# pc_healthypi_5_2_display_st7796.net
KiCad netlist of a schematic drawn in EAGLE
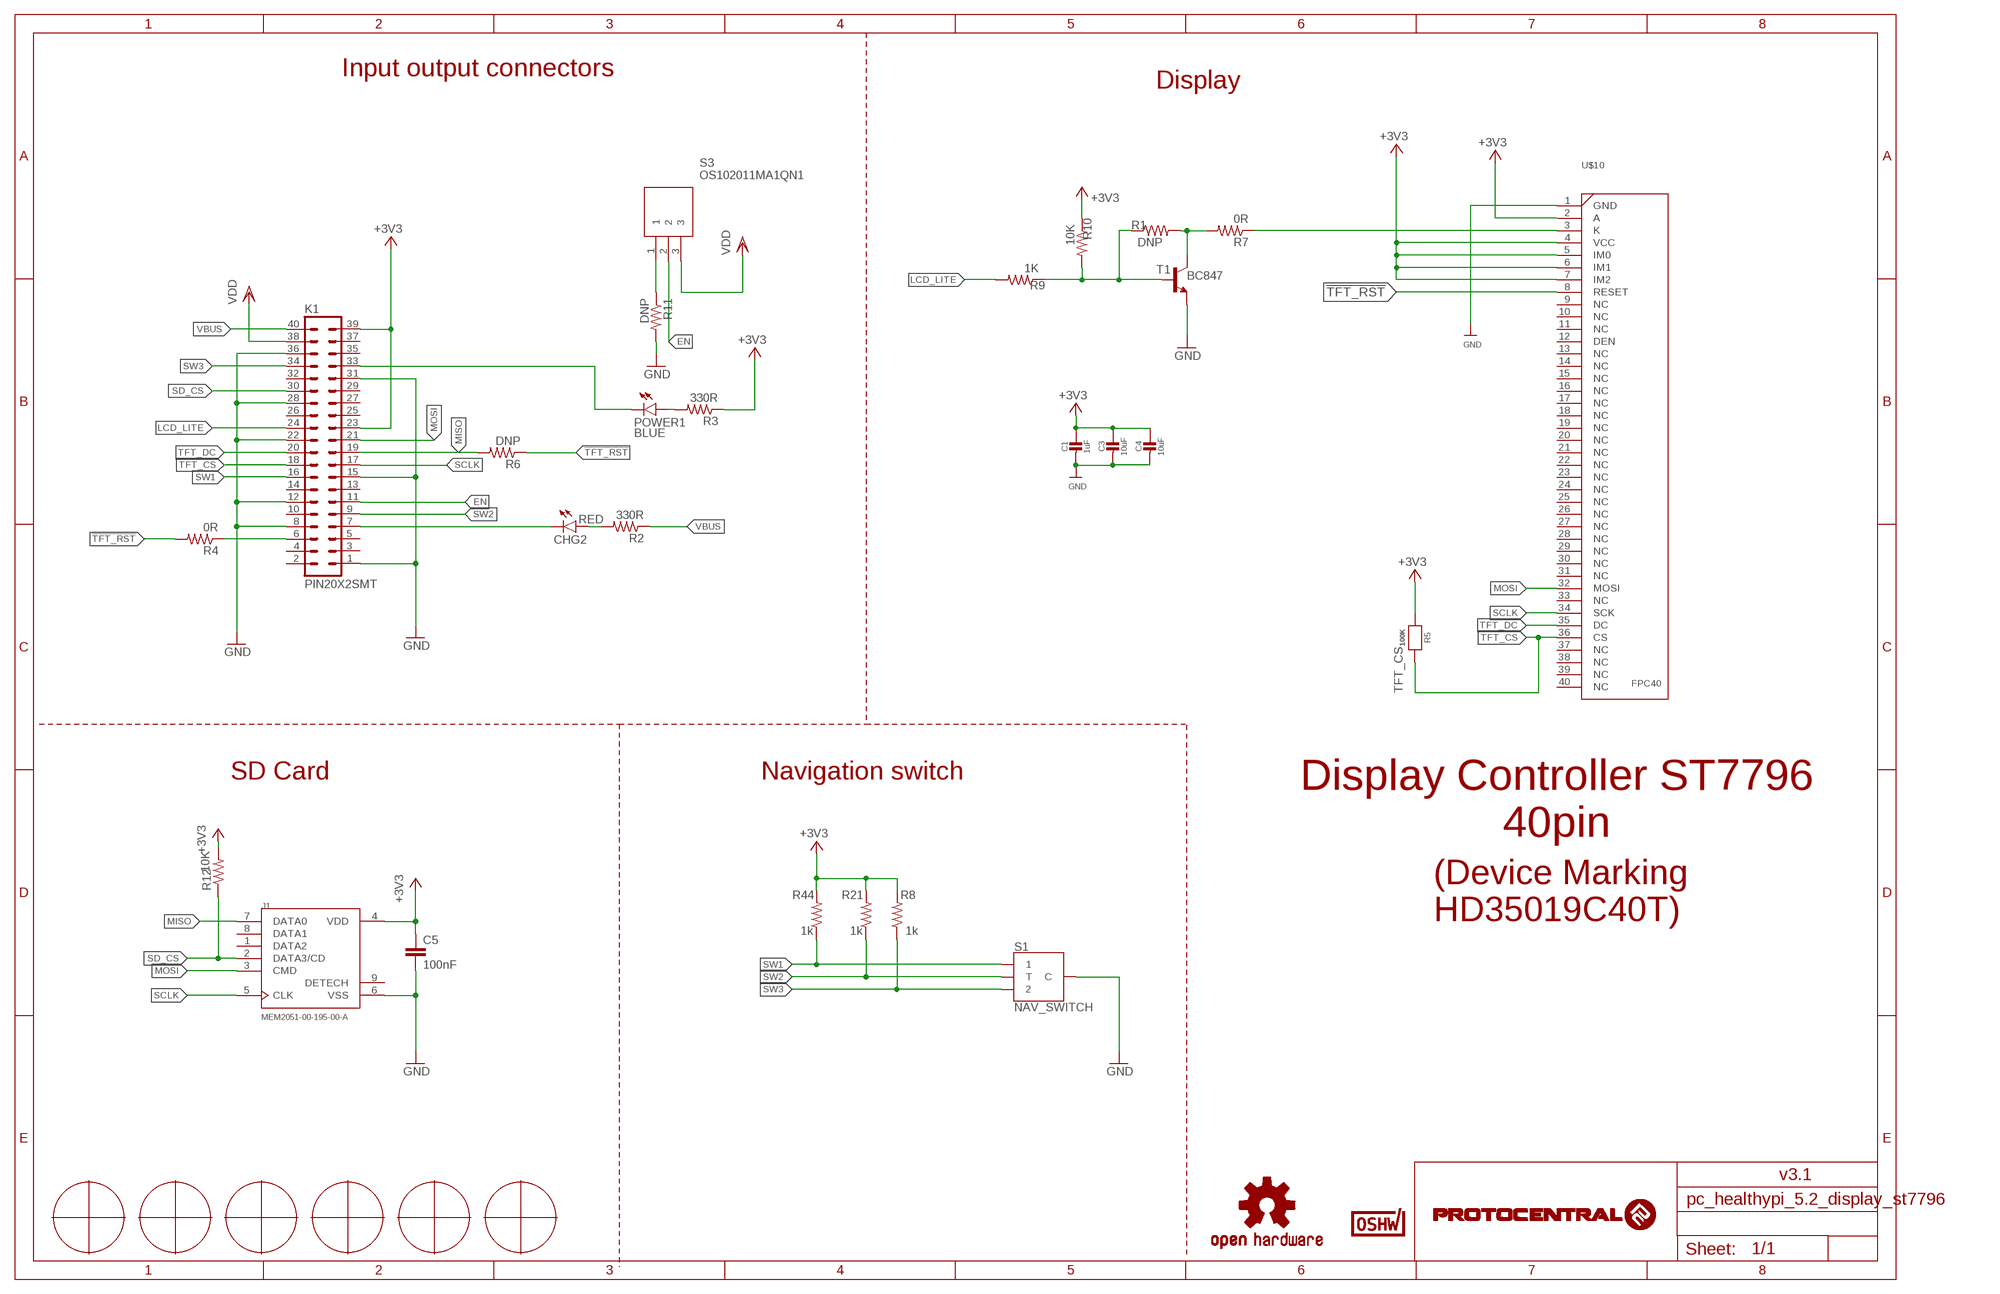
[diagram p0: schematic, sheet 1]

(export (version "E")
  (design (tool "Eeschema 10.0.6"))
  (components
    (comp (ref "C1")
      (value "1uF")
      (footprint "eagle-import:0805-NO")
      (libsource (lib "eagle-import") (part "CAP_CERAMIC0805-NOOUTLINE"))
    )
    (comp (ref "C3")
      (value "10uF")
      (footprint "eagle-import:0805-NO")
      (libsource (lib "eagle-import") (part "CAP_CERAMIC0805-NOOUTLINE"))
    )
    (comp (ref "C4")
      (value "10uF")
      (footprint "eagle-import:0805-NO")
      (libsource (lib "eagle-import") (part "CAP_CERAMIC0805-NOOUTLINE"))
    )
    (comp (ref "C5")
      (value "100nF")
      (footprint "eagle-import:C0402")
      (libsource (lib "eagle-import") (part "C-EUC0402"))
    )
    (comp (ref "CHG2")
      (value "RED")
      (footprint "eagle-import:CHIPLED_0603")
      (libsource (lib "eagle-import") (part "LEDCHIPLED_0603"))
    )
    (comp (ref "J1")
      (value "MEM2051-00-195-00-A")
      (footprint "eagle-import:GCT_MEM2051-00-195-00-A")
      (fields (field (name "MF") "Global Connector Technology"))
      (libsource (lib "eagle-import") (part "MEM2051-00-195-00-A"))
    )
    (comp (ref "K1")
      (value "PIN20X2SMT")
      (footprint "eagle-import:20X2SMT")
      (libsource (lib "eagle-import") (part "PIN20X2SMT"))
    )
    (comp (ref "POWER1")
      (value "BLUE")
      (footprint "eagle-import:CHIPLED_0603")
      (libsource (lib "eagle-import") (part "LEDCHIPLED_0603"))
    )
    (comp (ref "R1")
      (value "DNP")
      (footprint "eagle-import:R0402")
      (libsource (lib "eagle-import") (part "rcl_334_R-US_R0402"))
    )
    (comp (ref "R2")
      (value "330R")
      (footprint "eagle-import:R0402")
      (libsource (lib "eagle-import") (part "rcl_334_R-US_R0402"))
    )
    (comp (ref "R3")
      (value "330R")
      (footprint "eagle-import:R0402")
      (libsource (lib "eagle-import") (part "rcl_334_R-US_R0402"))
    )
    (comp (ref "R4")
      (value "0R")
      (footprint "eagle-import:R0402")
      (libsource (lib "eagle-import") (part "rcl_334_R-US_R0402"))
    )
    (comp (ref "R5")
      (value "100K")
      (footprint "eagle-import:0805-NO")
      (libsource (lib "eagle-import") (part "RESISTOR0805_NOOUTLINE"))
    )
    (comp (ref "R6")
      (value "DNP")
      (footprint "eagle-import:R0402")
      (libsource (lib "eagle-import") (part "rcl_334_R-US_R0402"))
    )
    (comp (ref "R7")
      (value "0R")
      (footprint "eagle-import:R0805")
      (libsource (lib "eagle-import") (part "rcl_334_R-US_R0805"))
    )
    (comp (ref "R8")
      (value "1k")
      (footprint "eagle-import:0402")
      (libsource (lib "eagle-import") (part "RESISTOR0402"))
    )
    (comp (ref "R9")
      (value "1K")
      (footprint "eagle-import:R0402")
      (libsource (lib "eagle-import") (part "rcl_334_R-US_R0402"))
    )
    (comp (ref "R10")
      (value "10K")
      (footprint "eagle-import:R0402")
      (libsource (lib "eagle-import") (part "rcl_334_R-US_R0402"))
    )
    (comp (ref "R11")
      (value "DNP")
      (footprint "eagle-import:R0402")
      (libsource (lib "eagle-import") (part "rcl_334_R-US_R0402"))
    )
    (comp (ref "R12")
      (value "10K")
      (footprint "eagle-import:R0402")
      (libsource (lib "eagle-import") (part "R-US_R0402"))
    )
    (comp (ref "R21")
      (value "1k")
      (footprint "eagle-import:0402")
      (libsource (lib "eagle-import") (part "RESISTOR0402"))
    )
    (comp (ref "R44")
      (value "1k")
      (footprint "eagle-import:0402")
      (libsource (lib "eagle-import") (part "RESISTOR0402"))
    )
    (comp (ref "S1")
      (value "NAV_SWITCH")
      (footprint "eagle-import:NAV_SWITCH")
      (libsource (lib "eagle-import") (part "NAV_SWITCH"))
    )
    (comp (ref "S3")
      (value "OS102011MA1QN1")
      (footprint "eagle-import:OS102011MA1QN1")
      (fields (field (name "MF") "C & K"))
      (libsource (lib "eagle-import") (part "OS102011MA1QN1"))
    )
    (comp (ref "T1")
      (value "BC847")
      (footprint "eagle-import:SOT23-BEC")
      (libsource (lib "eagle-import") (part "-NPN-SOT23-BECMMBT2222ALT1"))
    )
    (comp (ref "U$1")
      (value "FUDCIALPOINTS")
      (footprint "eagle-import:FIDUCIALPOINTS")
      (libsource (lib "eagle-import") (part "FUDCIALPOINTS"))
    )
    (comp (ref "U$3")
      (value "FUDCIALPOINTS")
      (footprint "eagle-import:FIDUCIALPOINTS")
      (libsource (lib "eagle-import") (part "FUDCIALPOINTS"))
    )
    (comp (ref "U$5")
      (value "OSHW-LOGOM")
      (footprint "eagle-import:OSHW-LOGO-M")
      (libsource (lib "eagle-import") (part "OSHW-LOGOM"))
    )
    (comp (ref "U$7")
      (value "FUDCIALPOINTS")
      (footprint "eagle-import:FIDUCIALPOINTS")
      (libsource (lib "eagle-import") (part "FUDCIALPOINTS"))
    )
    (comp (ref "U$8")
      (value "FUDCIALPOINTS")
      (footprint "eagle-import:FIDUCIALPOINTS")
      (libsource (lib "eagle-import") (part "FUDCIALPOINTS"))
    )
    (comp (ref "U$10")
      (value "FPC40")
      (footprint "eagle-import:FPC40PIN")
      (libsource (lib "eagle-import") (part "FPC40"))
    )
    (comp (ref "U$13")
      (value "CERT-SMALL")
      (footprint "eagle-import:CERT-SMALL-SILK")
      (libsource (lib "eagle-import") (part "CERT-SMALL"))
    )
    (comp (ref "U$23")
      (value "FUDCIALPOINTS")
      (footprint "eagle-import:FIDUCIALPOINTS")
      (libsource (lib "eagle-import") (part "FUDCIALPOINTS"))
    )
    (comp (ref "U$25")
      (value "FUDCIALPOINTS")
      (footprint "eagle-import:FIDUCIALPOINTS")
      (libsource (lib "eagle-import") (part "FUDCIALPOINTS"))
    )
  )
  (nets
    (net (code "1") (name "+3V3") (class "Default")
      (node (ref "C1") (pin "1") (pinfunction "1_1") (pintype "passive"))
      (node (ref "C3") (pin "1") (pinfunction "1_1") (pintype "passive"))
      (node (ref "C4") (pin "1") (pinfunction "1_1") (pintype "passive"))
      (node (ref "C5") (pin "1") (pinfunction "1_1") (pintype "passive"))
      (node (ref "J1") (pin "4") (pinfunction "VDD_4") (pintype "power_in"))
      (node (ref "K1") (pin "23") (pinfunction "23_23") (pintype "passive"))
      (node (ref "K1") (pin "39") (pinfunction "39_39") (pintype "passive"))
      (node (ref "R10") (pin "1") (pinfunction "1_1") (pintype "passive"))
      (node (ref "R12") (pin "2") (pinfunction "2_2") (pintype "passive"))
      (node (ref "R21") (pin "2") (pinfunction "2_2") (pintype "passive"))
      (node (ref "R3") (pin "1") (pinfunction "1_1") (pintype "passive"))
      (node (ref "R44") (pin "2") (pinfunction "2_2") (pintype "passive"))
      (node (ref "R5") (pin "2") (pinfunction "2_2") (pintype "passive"))
      (node (ref "R8") (pin "2") (pinfunction "2_2") (pintype "passive"))
      (node (ref "U$10") (pin "2") (pinfunction "A_2") (pintype "bidirectional"))
      (node (ref "U$10") (pin "4") (pinfunction "VCC_4") (pintype "bidirectional"))
      (node (ref "U$10") (pin "5") (pinfunction "IM0_5") (pintype "bidirectional"))
      (node (ref "U$10") (pin "6") (pinfunction "IM1_6") (pintype "bidirectional"))
      (node (ref "U$10") (pin "7") (pinfunction "IM2_7") (pintype "bidirectional"))
    )
    (net (code "2") (name "/~{TFT_RST}") (class "Default")
      (node (ref "R4") (pin "2") (pinfunction "2_2") (pintype "passive"))
      (node (ref "R6") (pin "1") (pinfunction "1_1") (pintype "passive"))
      (node (ref "U$10") (pin "8") (pinfunction "RESET_8") (pintype "bidirectional"))
    )
    (net (code "3") (name "EN") (class "Default")
      (node (ref "K1") (pin "11") (pinfunction "11_11") (pintype "passive"))
      (node (ref "S3") (pin "2") (pinfunction "2_2") (pintype "bidirectional"))
    )
    (net (code "4") (name "GND") (class "Default")
      (node (ref "C1") (pin "2") (pinfunction "2_2") (pintype "passive"))
      (node (ref "C3") (pin "2") (pinfunction "2_2") (pintype "passive"))
      (node (ref "C4") (pin "2") (pinfunction "2_2") (pintype "passive"))
      (node (ref "C5") (pin "2") (pinfunction "2_2") (pintype "passive"))
      (node (ref "J1") (pin "6") (pinfunction "VSS_6") (pintype "power_in"))
      (node (ref "K1") (pin "1") (pinfunction "1_1") (pintype "passive"))
      (node (ref "K1") (pin "12") (pinfunction "12_12") (pintype "passive"))
      (node (ref "K1") (pin "15") (pinfunction "15_15") (pintype "passive"))
      (node (ref "K1") (pin "22") (pinfunction "22_22") (pintype "passive"))
      (node (ref "K1") (pin "28") (pinfunction "28_28") (pintype "passive"))
      (node (ref "K1") (pin "31") (pinfunction "31_31") (pintype "passive"))
      (node (ref "K1") (pin "36") (pinfunction "36_36") (pintype "passive"))
      (node (ref "K1") (pin "8") (pinfunction "8_8") (pintype "passive"))
      (node (ref "R11") (pin "2") (pinfunction "2_2") (pintype "passive"))
      (node (ref "S1") (pin "C") (pinfunction "C_C") (pintype "power_in"))
      (node (ref "T1") (pin "E") (pinfunction "E_E") (pintype "passive"))
      (node (ref "U$10") (pin "1") (pinfunction "GND_1") (pintype "bidirectional"))
    )
    (net (code "5") (name "LCD_LITE") (class "Default")
      (node (ref "K1") (pin "24") (pinfunction "24_24") (pintype "passive"))
      (node (ref "R9") (pin "2") (pinfunction "2_2") (pintype "passive"))
    )
    (net (code "6") (name "MISO") (class "Default")
      (node (ref "J1") (pin "7") (pinfunction "DATA0_7") (pintype "bidirectional"))
      (node (ref "K1") (pin "19") (pinfunction "19_19") (pintype "passive"))
      (node (ref "R6") (pin "2") (pinfunction "2_2") (pintype "passive"))
    )
    (net (code "7") (name "MOSI") (class "Default")
      (node (ref "J1") (pin "3") (pinfunction "CMD_3") (pintype "bidirectional"))
      (node (ref "K1") (pin "21") (pinfunction "21_21") (pintype "passive"))
      (node (ref "U$10") (pin "32") (pinfunction "MOSI_32") (pintype "bidirectional"))
    )
    (net (code "8") (name "Net-(CHG2-PadA)") (class "Default")
      (node (ref "CHG2") (pin "A") (pinfunction "A_A") (pintype "passive"))
      (node (ref "R2") (pin "2") (pinfunction "2_2") (pintype "passive"))
    )
    (net (code "9") (name "Net-(CHG2-PadC)") (class "Default")
      (node (ref "CHG2") (pin "C") (pinfunction "C_C") (pintype "passive"))
      (node (ref "K1") (pin "7") (pinfunction "7_7") (pintype "passive"))
    )
    (net (code "10") (name "Net-(K1-Pad6)") (class "Default")
      (node (ref "K1") (pin "6") (pinfunction "6_6") (pintype "passive"))
      (node (ref "R4") (pin "1") (pinfunction "1_1") (pintype "passive"))
    )
    (net (code "11") (name "Net-(K1-Pad33)") (class "Default")
      (node (ref "K1") (pin "33") (pinfunction "33_33") (pintype "passive"))
      (node (ref "POWER1") (pin "C") (pinfunction "C_C") (pintype "passive"))
    )
    (net (code "12") (name "Net-(POWER1-PadA)") (class "Default")
      (node (ref "POWER1") (pin "A") (pinfunction "A_A") (pintype "passive"))
      (node (ref "R3") (pin "2") (pinfunction "2_2") (pintype "passive"))
    )
    (net (code "13") (name "Net-(R1-Pad1)") (class "Default")
      (node (ref "R1") (pin "1") (pinfunction "1_1") (pintype "passive"))
      (node (ref "R10") (pin "2") (pinfunction "2_2") (pintype "passive"))
      (node (ref "R9") (pin "1") (pinfunction "1_1") (pintype "passive"))
      (node (ref "T1") (pin "B") (pinfunction "B_B") (pintype "passive"))
    )
    (net (code "14") (name "Net-(R1-Pad2)") (class "Default")
      (node (ref "R1") (pin "2") (pinfunction "2_2") (pintype "passive"))
      (node (ref "R7") (pin "2") (pinfunction "2_2") (pintype "passive"))
      (node (ref "T1") (pin "C") (pinfunction "C_C") (pintype "passive"))
    )
    (net (code "15") (name "Net-(R11-Pad1)") (class "Default")
      (node (ref "R11") (pin "1") (pinfunction "1_1") (pintype "passive"))
      (node (ref "S3") (pin "1") (pinfunction "1_1") (pintype "bidirectional"))
    )
    (net (code "16") (name "Net-(U$10-K)") (class "Default")
      (node (ref "R7") (pin "1") (pinfunction "1_1") (pintype "passive"))
      (node (ref "U$10") (pin "3") (pinfunction "K_3") (pintype "bidirectional"))
    )
    (net (code "17") (name "SCLK") (class "Default")
      (node (ref "J1") (pin "5") (pinfunction "CLK_5") (pintype "bidirectional"))
      (node (ref "K1") (pin "17") (pinfunction "17_17") (pintype "passive"))
      (node (ref "U$10") (pin "34") (pinfunction "SCK_34") (pintype "bidirectional"))
    )
    (net (code "18") (name "SD_CS") (class "Default")
      (node (ref "J1") (pin "2") (pinfunction "DATA3/CD_2") (pintype "bidirectional"))
      (node (ref "K1") (pin "30") (pinfunction "30_30") (pintype "passive"))
      (node (ref "R12") (pin "1") (pinfunction "1_1") (pintype "passive"))
    )
    (net (code "19") (name "SW1") (class "Default")
      (node (ref "K1") (pin "16") (pinfunction "16_16") (pintype "passive"))
      (node (ref "R44") (pin "1") (pinfunction "1_1") (pintype "passive"))
      (node (ref "S1") (pin "1") (pinfunction "1_1") (pintype "input"))
    )
    (net (code "20") (name "SW2") (class "Default")
      (node (ref "K1") (pin "9") (pinfunction "9_9") (pintype "passive"))
      (node (ref "R21") (pin "1") (pinfunction "1_1") (pintype "passive"))
      (node (ref "S1") (pin "T") (pinfunction "T_T") (pintype "input"))
    )
    (net (code "21") (name "SW3") (class "Default")
      (node (ref "K1") (pin "34") (pinfunction "34_34") (pintype "passive"))
      (node (ref "R8") (pin "1") (pinfunction "1_1") (pintype "passive"))
      (node (ref "S1") (pin "2") (pinfunction "2_2") (pintype "input"))
    )
    (net (code "22") (name "TFT_CS") (class "Default")
      (node (ref "K1") (pin "18") (pinfunction "18_18") (pintype "passive"))
      (node (ref "R5") (pin "1") (pinfunction "1_1") (pintype "passive"))
      (node (ref "U$10") (pin "36") (pinfunction "CS_36") (pintype "bidirectional"))
    )
    (net (code "23") (name "TFT_DC") (class "Default")
      (node (ref "K1") (pin "20") (pinfunction "20_20") (pintype "passive"))
      (node (ref "U$10") (pin "35") (pinfunction "DC_35") (pintype "bidirectional"))
    )
    (net (code "24") (name "VBUS") (class "Default")
      (node (ref "K1") (pin "40") (pinfunction "40_40") (pintype "passive"))
      (node (ref "R2") (pin "1") (pinfunction "1_1") (pintype "passive"))
    )
    (net (code "25") (name "VDD") (class "Default")
      (node (ref "K1") (pin "38") (pinfunction "38_38") (pintype "passive"))
      (node (ref "S3") (pin "3") (pinfunction "3_3") (pintype "bidirectional"))
    )
    (net (code "26") (name "unconnected-(J1-DATA1-Pad8)") (class "Default")
      (node (ref "J1") (pin "8") (pinfunction "DATA1_8") (pintype "bidirectional"))
    )
    (net (code "27") (name "unconnected-(J1-DATA2-Pad1)") (class "Default")
      (node (ref "J1") (pin "1") (pinfunction "DATA2_1") (pintype "bidirectional"))
    )
    (net (code "28") (name "unconnected-(J1-DETECH-Pad9)") (class "Default")
      (node (ref "J1") (pin "9") (pinfunction "DETECH_9") (pintype "passive"))
    )
    (net (code "29") (name "unconnected-(K1-Pad2)") (class "Default")
      (node (ref "K1") (pin "2") (pinfunction "2_2") (pintype "passive"))
    )
    (net (code "30") (name "unconnected-(K1-Pad3)") (class "Default")
      (node (ref "K1") (pin "3") (pinfunction "3_3") (pintype "passive"))
    )
    (net (code "31") (name "unconnected-(K1-Pad4)") (class "Default")
      (node (ref "K1") (pin "4") (pinfunction "4_4") (pintype "passive"))
    )
    (net (code "32") (name "unconnected-(K1-Pad5)") (class "Default")
      (node (ref "K1") (pin "5") (pinfunction "5_5") (pintype "passive"))
    )
    (net (code "33") (name "unconnected-(K1-Pad10)") (class "Default")
      (node (ref "K1") (pin "10") (pinfunction "10_10") (pintype "passive"))
    )
    (net (code "34") (name "unconnected-(K1-Pad13)") (class "Default")
      (node (ref "K1") (pin "13") (pinfunction "13_13") (pintype "passive"))
    )
    (net (code "35") (name "unconnected-(K1-Pad14)") (class "Default")
      (node (ref "K1") (pin "14") (pinfunction "14_14") (pintype "passive"))
    )
    (net (code "36") (name "unconnected-(K1-Pad25)") (class "Default")
      (node (ref "K1") (pin "25") (pinfunction "25_25") (pintype "passive"))
    )
    (net (code "37") (name "unconnected-(K1-Pad26)") (class "Default")
      (node (ref "K1") (pin "26") (pinfunction "26_26") (pintype "passive"))
    )
    (net (code "38") (name "unconnected-(K1-Pad27)") (class "Default")
      (node (ref "K1") (pin "27") (pinfunction "27_27") (pintype "passive"))
    )
    (net (code "39") (name "unconnected-(K1-Pad29)") (class "Default")
      (node (ref "K1") (pin "29") (pinfunction "29_29") (pintype "passive"))
    )
    (net (code "40") (name "unconnected-(K1-Pad32)") (class "Default")
      (node (ref "K1") (pin "32") (pinfunction "32_32") (pintype "passive"))
    )
    (net (code "41") (name "unconnected-(K1-Pad35)") (class "Default")
      (node (ref "K1") (pin "35") (pinfunction "35_35") (pintype "passive"))
    )
    (net (code "42") (name "unconnected-(K1-Pad37)") (class "Default")
      (node (ref "K1") (pin "37") (pinfunction "37_37") (pintype "passive"))
    )
    (net (code "43") (name "unconnected-(U$10-DEN-Pad12)") (class "Default")
      (node (ref "U$10") (pin "12") (pinfunction "DEN_12") (pintype "bidirectional"))
    )
    (net (code "44") (name "unconnected-(U$10-NC-Pad9)") (class "Default")
      (node (ref "U$10") (pin "9") (pinfunction "NC_9") (pintype "bidirectional"))
    )
    (net (code "45") (name "unconnected-(U$10-NC-Pad10)") (class "Default")
      (node (ref "U$10") (pin "10") (pinfunction "NC_10") (pintype "bidirectional"))
    )
    (net (code "46") (name "unconnected-(U$10-NC-Pad11)") (class "Default")
      (node (ref "U$10") (pin "11") (pinfunction "NC_11") (pintype "bidirectional"))
    )
    (net (code "47") (name "unconnected-(U$10-NC-Pad13)") (class "Default")
      (node (ref "U$10") (pin "13") (pinfunction "NC_13") (pintype "bidirectional"))
    )
    (net (code "48") (name "unconnected-(U$10-NC-Pad14)") (class "Default")
      (node (ref "U$10") (pin "14") (pinfunction "NC_14") (pintype "bidirectional"))
    )
    (net (code "49") (name "unconnected-(U$10-NC-Pad15)") (class "Default")
      (node (ref "U$10") (pin "15") (pinfunction "NC_15") (pintype "bidirectional"))
    )
    (net (code "50") (name "unconnected-(U$10-NC-Pad16)") (class "Default")
      (node (ref "U$10") (pin "16") (pinfunction "NC_16") (pintype "bidirectional"))
    )
    (net (code "51") (name "unconnected-(U$10-NC-Pad17)") (class "Default")
      (node (ref "U$10") (pin "17") (pinfunction "NC_17") (pintype "bidirectional"))
    )
    (net (code "52") (name "unconnected-(U$10-NC-Pad18)") (class "Default")
      (node (ref "U$10") (pin "18") (pinfunction "NC_18") (pintype "bidirectional"))
    )
    (net (code "53") (name "unconnected-(U$10-NC-Pad19)") (class "Default")
      (node (ref "U$10") (pin "19") (pinfunction "NC_19") (pintype "bidirectional"))
    )
    (net (code "54") (name "unconnected-(U$10-NC-Pad20)") (class "Default")
      (node (ref "U$10") (pin "20") (pinfunction "NC_20") (pintype "bidirectional"))
    )
    (net (code "55") (name "unconnected-(U$10-NC-Pad21)") (class "Default")
      (node (ref "U$10") (pin "21") (pinfunction "NC_21") (pintype "bidirectional"))
    )
    (net (code "56") (name "unconnected-(U$10-NC-Pad22)") (class "Default")
      (node (ref "U$10") (pin "22") (pinfunction "NC_22") (pintype "bidirectional"))
    )
    (net (code "57") (name "unconnected-(U$10-NC-Pad23)") (class "Default")
      (node (ref "U$10") (pin "23") (pinfunction "NC_23") (pintype "bidirectional"))
    )
    (net (code "58") (name "unconnected-(U$10-NC-Pad24)") (class "Default")
      (node (ref "U$10") (pin "24") (pinfunction "NC_24") (pintype "bidirectional"))
    )
    (net (code "59") (name "unconnected-(U$10-NC-Pad25)") (class "Default")
      (node (ref "U$10") (pin "25") (pinfunction "NC_25") (pintype "bidirectional"))
    )
    (net (code "60") (name "unconnected-(U$10-NC-Pad26)") (class "Default")
      (node (ref "U$10") (pin "26") (pinfunction "NC_26") (pintype "bidirectional"))
    )
    (net (code "61") (name "unconnected-(U$10-NC-Pad27)") (class "Default")
      (node (ref "U$10") (pin "27") (pinfunction "NC_27") (pintype "bidirectional"))
    )
    (net (code "62") (name "unconnected-(U$10-NC-Pad28)") (class "Default")
      (node (ref "U$10") (pin "28") (pinfunction "NC_28") (pintype "bidirectional"))
    )
    (net (code "63") (name "unconnected-(U$10-NC-Pad29)") (class "Default")
      (node (ref "U$10") (pin "29") (pinfunction "NC_29") (pintype "bidirectional"))
    )
    (net (code "64") (name "unconnected-(U$10-NC-Pad30)") (class "Default")
      (node (ref "U$10") (pin "30") (pinfunction "NC_30") (pintype "bidirectional"))
    )
    (net (code "65") (name "unconnected-(U$10-NC-Pad31)") (class "Default")
      (node (ref "U$10") (pin "31") (pinfunction "NC_31") (pintype "bidirectional"))
    )
    (net (code "66") (name "unconnected-(U$10-NC-Pad33)") (class "Default")
      (node (ref "U$10") (pin "33") (pinfunction "NC_33") (pintype "bidirectional"))
    )
    (net (code "67") (name "unconnected-(U$10-NC-Pad37)") (class "Default")
      (node (ref "U$10") (pin "37") (pinfunction "NC_37") (pintype "bidirectional"))
    )
    (net (code "68") (name "unconnected-(U$10-NC-Pad38)") (class "Default")
      (node (ref "U$10") (pin "38") (pinfunction "NC_38") (pintype "bidirectional"))
    )
    (net (code "69") (name "unconnected-(U$10-NC-Pad39)") (class "Default")
      (node (ref "U$10") (pin "39") (pinfunction "NC_39") (pintype "bidirectional"))
    )
    (net (code "70") (name "unconnected-(U$10-NC-Pad40)") (class "Default")
      (node (ref "U$10") (pin "40") (pinfunction "NC_40") (pintype "bidirectional"))
    )
  )
)
